# fig3.net
KiCad netlist of a schematic drawn in EasyEDA
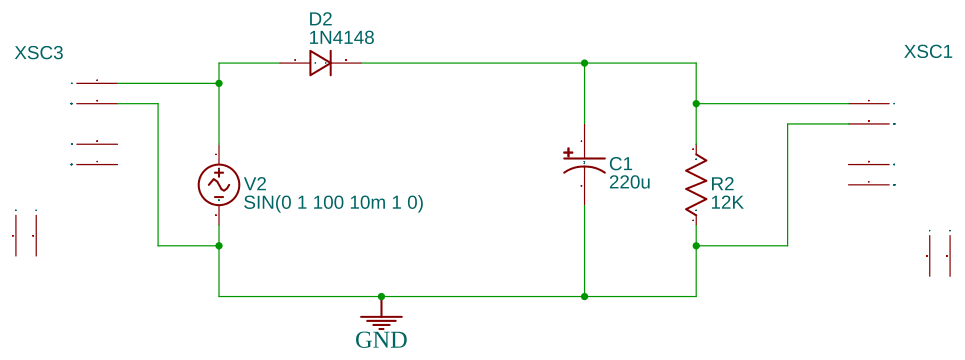
[diagram p0: schematic sheet]

(export (version "E")
  (design (tool "Eeschema 10.0.6"))
  (components
    (comp (ref "C1") (value "220u") (libsource (lib "") (part "Capacitor_Electrolytic_US")))
    (comp (ref "D2") (value "1N4148") (libsource (lib "") (part "1N4148")))
    (comp (ref "R2") (value "12K") (libsource (lib "") (part "Resistor_US")))
    (comp (ref "V2") (value "SIN(0 1 100 10m 1 0)") (libsource (lib "") (part "VSin")))
    (comp (ref "XSC1") (value "Oscilloscope") (libsource (lib "") (part "OSCILLOSCOPE")))
    (comp (ref "XSC3") (value "Oscilloscope") (libsource (lib "") (part "OSCILLOSCOPE_1")))
  )
  (nets
    (net (code "1") (name "GND") (class "Default")
      (node (ref "C1") (pin "2") (pinfunction "2_2") (pintype "unspecified"))
      (node (ref "R2") (pin "1") (pinfunction "1_1") (pintype "unspecified"))
      (node (ref "V2") (pin "2") (pinfunction "2_2") (pintype "unspecified"))
      (node (ref "XSC1") (pin "2") (pinfunction "GND1_2") (pintype "unspecified"))
      (node (ref "XSC3") (pin "2") (pinfunction "GND1_2") (pintype "unspecified"))
    )
    (net (code "2") (name "Net-(D2-A)") (class "Default")
      (node (ref "D2") (pin "1") (pinfunction "A_1") (pintype "unspecified"))
      (node (ref "V2") (pin "1") (pinfunction "1_1") (pintype "unspecified"))
      (node (ref "XSC3") (pin "1") (pinfunction "A_1") (pintype "unspecified"))
    )
    (net (code "3") (name "Net-(D2-K)") (class "Default")
      (node (ref "C1") (pin "1") (pinfunction "1_1") (pintype "unspecified"))
      (node (ref "D2") (pin "2") (pinfunction "K_2") (pintype "unspecified"))
      (node (ref "R2") (pin "2") (pinfunction "2_2") (pintype "unspecified"))
      (node (ref "XSC1") (pin "1") (pinfunction "A_1") (pintype "unspecified"))
    )
    (net (code "4") (name "unconnected-(XSC1-B-Pad3)") (class "Default")
      (node (ref "XSC1") (pin "3") (pinfunction "B_3") (pintype "unspecified"))
    )
    (net (code "5") (name "unconnected-(XSC1-GND2-Pad4)") (class "Default")
      (node (ref "XSC1") (pin "4") (pinfunction "GND2_4") (pintype "unspecified"))
    )
    (net (code "6") (name "unconnected-(XSC1-T+-Pad5)") (class "Default")
      (node (ref "XSC1") (pin "5") (pinfunction "T+_5") (pintype "unspecified"))
    )
    (net (code "7") (name "unconnected-(XSC1-T--Pad6)") (class "Default")
      (node (ref "XSC1") (pin "6") (pinfunction "T-_6") (pintype "unspecified"))
    )
    (net (code "8") (name "unconnected-(XSC3-B-Pad3)") (class "Default")
      (node (ref "XSC3") (pin "3") (pinfunction "B_3") (pintype "unspecified"))
    )
    (net (code "9") (name "unconnected-(XSC3-GND2-Pad4)") (class "Default")
      (node (ref "XSC3") (pin "4") (pinfunction "GND2_4") (pintype "unspecified"))
    )
    (net (code "10") (name "unconnected-(XSC3-T+-Pad5)") (class "Default")
      (node (ref "XSC3") (pin "5") (pinfunction "T+_5") (pintype "unspecified"))
    )
    (net (code "11") (name "unconnected-(XSC3-T--Pad6)") (class "Default")
      (node (ref "XSC3") (pin "6") (pinfunction "T-_6") (pintype "unspecified"))
    )
  )
)
